# VGA.net
KiCad netlist of a schematic drawn in Altium Designer
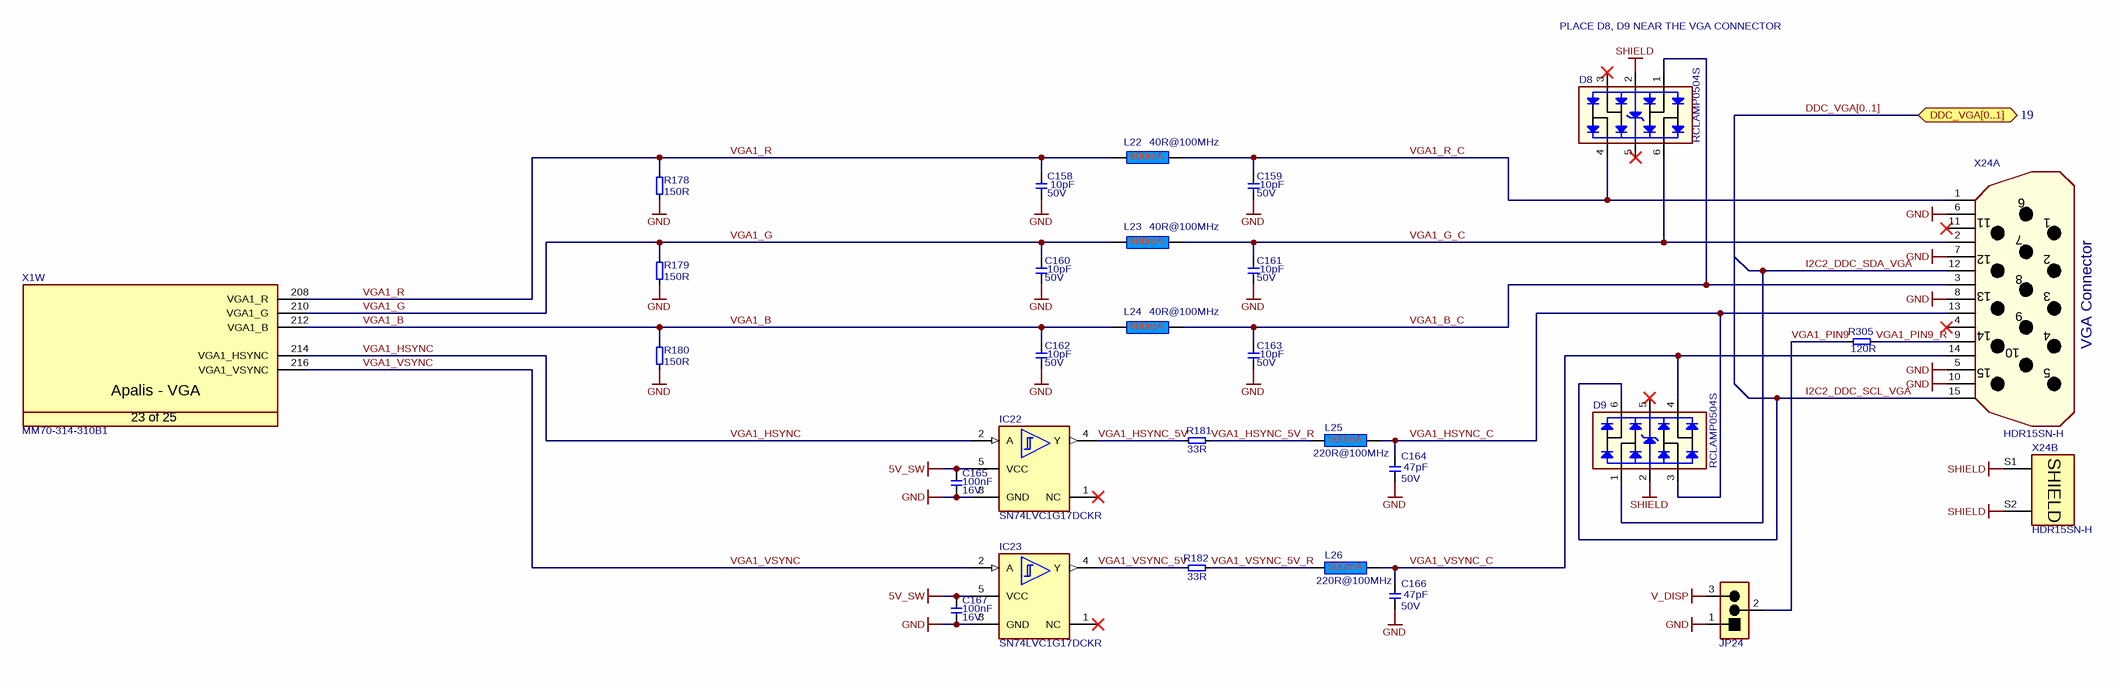
[diagram p0: VGA.SchDoc]

(export (version "E")
  (design (tool "Eeschema 10.0.6"))
  (components
    (comp (ref "C158")
      (value "10pF")
      (footprint "T_CAPC0603X33N")
      (description "Capacitor Ceramic NP0 10pF 50V 10% 0603")
      (fields (field (name "TOLERANCE") "10%") (field (name "RATING") "50V"))
      (libsource (lib "Apalis Evaluation Board") (part "C-NP0-10pF-50V-10%-0603"))
    )
    (comp (ref "C159")
      (value "10pF")
      (footprint "T_CAPC0603X33N")
      (description "Capacitor Ceramic NP0 10pF 50V 10% 0603")
      (fields (field (name "TOLERANCE") "10%") (field (name "RATING") "50V"))
      (libsource (lib "Apalis Evaluation Board") (part "C-NP0-10pF-50V-10%-0603"))
    )
    (comp (ref "C160")
      (value "10pF")
      (footprint "T_CAPC0603X33N")
      (description "Capacitor Ceramic NP0 10pF 50V 10% 0603")
      (fields (field (name "TOLERANCE") "10%") (field (name "RATING") "50V"))
      (libsource (lib "Apalis Evaluation Board") (part "C-NP0-10pF-50V-10%-0603"))
    )
    (comp (ref "C161")
      (value "10pF")
      (footprint "T_CAPC0603X33N")
      (description "Capacitor Ceramic NP0 10pF 50V 10% 0603")
      (fields (field (name "TOLERANCE") "10%") (field (name "RATING") "50V"))
      (libsource (lib "Apalis Evaluation Board") (part "C-NP0-10pF-50V-10%-0603"))
    )
    (comp (ref "C162")
      (value "10pF")
      (footprint "T_CAPC0603X33N")
      (description "Capacitor Ceramic NP0 10pF 50V 10% 0603")
      (fields (field (name "TOLERANCE") "10%") (field (name "RATING") "50V"))
      (libsource (lib "Apalis Evaluation Board") (part "C-NP0-10pF-50V-10%-0603"))
    )
    (comp (ref "C163")
      (value "10pF")
      (footprint "T_CAPC0603X33N")
      (description "Capacitor Ceramic NP0 10pF 50V 10% 0603")
      (fields (field (name "TOLERANCE") "10%") (field (name "RATING") "50V"))
      (libsource (lib "Apalis Evaluation Board") (part "C-NP0-10pF-50V-10%-0603"))
    )
    (comp (ref "C164")
      (value "47pF")
      (footprint "T_CAPC0603X33N")
      (description "Capacitor Ceramic NP0 47pF 50V 10% 0603")
      (fields (field (name "TOLERANCE") "10%") (field (name "RATING") "50V"))
      (libsource (lib "Apalis Evaluation Board") (part "C-NP0-47pF-50V-10%-0603"))
    )
    (comp (ref "C165")
      (value "100nF")
      (footprint "T_CAPC0603X33N")
      (description "Capacitor Ceramic X7R 100nF 16V 10% 0603")
      (fields (field (name "TOLERANCE") "10%") (field (name "RATING") "16V"))
      (libsource (lib "Apalis Evaluation Board") (part "C-X7R-100nF-16V-10%-0603"))
    )
    (comp (ref "C166")
      (value "47pF")
      (footprint "T_CAPC0603X33N")
      (description "Capacitor Ceramic NP0 47pF 50V 10% 0603")
      (fields (field (name "TOLERANCE") "10%") (field (name "RATING") "50V"))
      (libsource (lib "Apalis Evaluation Board") (part "C-NP0-47pF-50V-10%-0603"))
    )
    (comp (ref "C167")
      (value "100nF")
      (footprint "T_CAPC0603X33N")
      (description "Capacitor Ceramic X7R 100nF 16V 10% 0603")
      (fields (field (name "TOLERANCE") "10%") (field (name "RATING") "16V"))
      (libsource (lib "Apalis Evaluation Board") (part "C-X7R-100nF-16V-10%-0603"))
    )
    (comp (ref "D8")
      (value "RCLAMP0504S")
      (footprint "T_SOT95P285X90-6N")
      (description "TVS Array low cap")
      (fields (field (name "MANUFACTURER PART NO.") "RCLAMP0504S"))
      (libsource (lib "Apalis Evaluation Board") (part "D-Semtech-RClamp0504S"))
    )
    (comp (ref "D9")
      (value "RCLAMP0504S")
      (footprint "T_SOT95P285X90-6N")
      (description "TVS Array low cap")
      (fields (field (name "MANUFACTURER PART NO.") "RCLAMP0504S"))
      (libsource (lib "") (part "D-Semtech-RClamp0504S_1"))
    )
    (comp (ref "IC22")
      (value "SN74LVC1G17DCKR")
      (footprint "SOT65P210X110-5N")
      (description "Single Schmitt-Trigger Buffer")
      (fields (field (name "MANUFACTURER PART NO.") "SN74LVC1G17DCKR"))
      (libsource (lib "Apalis Evaluation Board") (part "IC-TI-SN74LVC1G17DCKR"))
    )
    (comp (ref "IC23")
      (value "SN74LVC1G17DCKR")
      (footprint "SOT65P210X110-5N")
      (description "Single Schmitt-Trigger Buffer")
      (fields (field (name "MANUFACTURER PART NO.") "SN74LVC1G17DCKR"))
      (libsource (lib "Apalis Evaluation Board") (part "IC-TI-SN74LVC1G17DCKR"))
    )
    (comp (ref "JP24")
      (value "826936-3")
      (footprint "T_TYCO_826936-3")
      (description "Jumper, 3-Pin")
      (libsource (lib "Apalis Evaluation Board") (part "CON-Tyco-826936-3-1X3-2.54mm-JP_1"))
    )
    (comp (ref "L22")
      (value "40R@100MHz")
      (footprint "INDC1608X95N")
      (description "40R@100MHz 600mA EMI FILTER")
      (fields (field (name "TOLERANCE") "25%") (field (name "MANUFACTURER PART NO.") "MMZ1608S400A"))
      (libsource (lib "Apalis Evaluation Board") (part "L-TDK-MMZ1608S400A-40R@100MHz-600mA-25%-0603"))
    )
    (comp (ref "L23")
      (value "40R@100MHz")
      (footprint "INDC1608X95N")
      (description "40R@100MHz 600mA EMI FILTER")
      (fields (field (name "TOLERANCE") "25%") (field (name "MANUFACTURER PART NO.") "MMZ1608S400A"))
      (libsource (lib "Apalis Evaluation Board") (part "L-TDK-MMZ1608S400A-40R@100MHz-600mA-25%-0603"))
    )
    (comp (ref "L24")
      (value "40R@100MHz")
      (footprint "INDC1608X95N")
      (description "40R@100MHz 600mA EMI FILTER")
      (fields (field (name "TOLERANCE") "25%") (field (name "MANUFACTURER PART NO.") "MMZ1608S400A"))
      (libsource (lib "Apalis Evaluation Board") (part "L-TDK-MMZ1608S400A-40R@100MHz-600mA-25%-0603"))
    )
    (comp (ref "L25")
      (value "220R@100MHz")
      (footprint "INDC1608X95N")
      (description "220R@100MHz 500mA EMI FILTER")
      (fields (field (name "TOLERANCE") "25%"))
      (libsource (lib "Apalis Evaluation Board") (part "L-220R@100MHz-500mA-25%-0603"))
    )
    (comp (ref "L26")
      (value "220R@100MHz")
      (footprint "INDC1608X95N")
      (description "220R@100MHz 500mA EMI FILTER")
      (fields (field (name "TOLERANCE") "25%"))
      (libsource (lib "Apalis Evaluation Board") (part "L-220R@100MHz-500mA-25%-0603"))
    )
    (comp (ref "R178")
      (value "150R")
      (footprint "T_RESC0603X30N")
      (description "Resistor 150 ohm 63mW 1% 0603")
      (fields (field (name "TOLERANCE") "1%"))
      (libsource (lib "Apalis Evaluation Board") (part "R-150R-63mW-1%-0603"))
    )
    (comp (ref "R179")
      (value "150R")
      (footprint "T_RESC0603X30N")
      (description "Resistor 150 ohm 63mW 1% 0603")
      (fields (field (name "TOLERANCE") "1%"))
      (libsource (lib "Apalis Evaluation Board") (part "R-150R-63mW-1%-0603"))
    )
    (comp (ref "R180")
      (value "150R")
      (footprint "T_RESC0603X30N")
      (description "Resistor 150 ohm 63mW 1% 0603")
      (fields (field (name "TOLERANCE") "1%"))
      (libsource (lib "Apalis Evaluation Board") (part "R-150R-63mW-1%-0603"))
    )
    (comp (ref "R181")
      (value "33R")
      (footprint "t_RESC0603X30N")
      (description "Resistor 33 ohm 63mW 5% 0603")
      (fields (field (name "TOLERANCE") "5%"))
      (libsource (lib "Apalis Evaluation Board") (part "R-33R-63mW-5%-0603"))
    )
    (comp (ref "R182")
      (value "33R")
      (footprint "t_RESC0603X30N")
      (description "Resistor 33 ohm 63mW 5% 0603")
      (fields (field (name "TOLERANCE") "5%"))
      (libsource (lib "Apalis Evaluation Board") (part "R-33R-63mW-5%-0603"))
    )
    (comp (ref "R305")
      (value "120R")
      (footprint "T_RESC0603X30N")
      (description "Resistor 120 ohm 250mW 5% 0603")
      (fields (field (name "TOLERANCE") "5%"))
      (libsource (lib "Apalis Evaluation Board") (part "R-120R-250mW-5%-0603"))
    )
    (comp (ref "X1")
      (value "CON-JAE-MM70-314-310B1-314-0.5mm")
      (footprint "T_JAE_MM70-314-310B1")
      (description "MXM3 Connector")
      (fields (field (name "MANUFACTURER PART NO.") "MM70-314-310B1"))
      (libsource (lib "Apalis Evaluation Board") (part "CON-JAE-MM70-314-310B1-314-0.5mm"))
    )
    (comp (ref "X24")
      (value "HDR15SN-H")
      (footprint "T_AUK_HDR15SN-H")
      (description "15 pin male D-SUB connector")
      (fields (field (name "MANUFACTURER PART NO.") "HDR15SN-H"))
      (libsource (lib "Apalis Evaluation Board") (part "CON-AUK-HDR15SN-H"))
    )
  )
  (nets
    (net (code "4") (name "/I2C2_DDC_SCL_VGA") (class "Default")
      (node (ref "D9") (pin "6") (pinfunction "6_6") (pintype "power_in"))
      (node (ref "X24") (pin "15") (pinfunction "RI_15") (pintype "passive"))
    )
    (net (code "5") (name "/I2C2_DDC_SDA_VGA") (class "Default")
      (node (ref "D9") (pin "1") (pinfunction "1_1") (pintype "power_in"))
      (node (ref "X24") (pin "12") (pinfunction "RI_12") (pintype "passive"))
    )
    (net (code "6") (name "/VGA1_B") (class "Default")
      (node (ref "C162") (pin "1") (pinfunction "1_1") (pintype "passive"))
      (node (ref "L24") (pin "1") (pinfunction "1_1") (pintype "passive"))
      (node (ref "R180") (pin "2") (pinfunction "2_2") (pintype "passive"))
      (node (ref "X1") (pin "212") (pinfunction "VGA1_B_212") (pintype "passive"))
    )
    (net (code "7") (name "/VGA1_B_C") (class "Default")
      (node (ref "C163") (pin "1") (pinfunction "1_1") (pintype "passive"))
      (node (ref "D8") (pin "1") (pinfunction "1_1") (pintype "power_in"))
      (node (ref "L24") (pin "2") (pinfunction "2_2") (pintype "passive"))
      (node (ref "X24") (pin "3") (pinfunction "TXD_3") (pintype "passive"))
    )
    (net (code "8") (name "/VGA1_G") (class "Default")
      (node (ref "C160") (pin "1") (pinfunction "1_1") (pintype "passive"))
      (node (ref "L23") (pin "1") (pinfunction "1_1") (pintype "passive"))
      (node (ref "R179") (pin "2") (pinfunction "2_2") (pintype "passive"))
      (node (ref "X1") (pin "210") (pinfunction "VGA1_G_210") (pintype "passive"))
    )
    (net (code "9") (name "/VGA1_G_C") (class "Default")
      (node (ref "C161") (pin "1") (pinfunction "1_1") (pintype "passive"))
      (node (ref "D8") (pin "6") (pinfunction "6_6") (pintype "power_in"))
      (node (ref "L23") (pin "2") (pinfunction "2_2") (pintype "passive"))
      (node (ref "X24") (pin "2") (pinfunction "RXD_2") (pintype "passive"))
    )
    (net (code "10") (name "/VGA1_HSYNC") (class "Default")
      (node (ref "IC22") (pin "2") (pinfunction "A_2") (pintype "input"))
      (node (ref "X1") (pin "214") (pinfunction "VGA1_HSYNC_214") (pintype "passive"))
    )
    (net (code "11") (name "/VGA1_HSYNC_5V") (class "Default")
      (node (ref "IC22") (pin "4") (pinfunction "Y_4") (pintype "output"))
      (node (ref "R181") (pin "1") (pinfunction "1_1") (pintype "passive"))
    )
    (net (code "12") (name "/VGA1_HSYNC_5V_R") (class "Default")
      (node (ref "L25") (pin "1") (pinfunction "1_1") (pintype "passive"))
      (node (ref "R181") (pin "2") (pinfunction "2_2") (pintype "passive"))
    )
    (net (code "13") (name "/VGA1_HSYNC_C") (class "Default")
      (node (ref "C164") (pin "1") (pinfunction "1_1") (pintype "passive"))
      (node (ref "D9") (pin "3") (pinfunction "3_3") (pintype "power_in"))
      (node (ref "L25") (pin "2") (pinfunction "2_2") (pintype "passive"))
      (node (ref "X24") (pin "13") (pinfunction "RI_13") (pintype "passive"))
    )
    (net (code "14") (name "/VGA1_PIN9") (class "Default")
      (node (ref "JP24") (pin "2") (pinfunction "2_2") (pintype "passive"))
      (node (ref "R305") (pin "1") (pinfunction "1_1") (pintype "passive"))
    )
    (net (code "15") (name "/VGA1_PIN9_R") (class "Default")
      (node (ref "R305") (pin "2") (pinfunction "2_2") (pintype "passive"))
      (node (ref "X24") (pin "9") (pinfunction "RI_9") (pintype "passive"))
    )
    (net (code "16") (name "/VGA1_R") (class "Default")
      (node (ref "C158") (pin "1") (pinfunction "1_1") (pintype "passive"))
      (node (ref "L22") (pin "1") (pinfunction "1_1") (pintype "passive"))
      (node (ref "R178") (pin "2") (pinfunction "2_2") (pintype "passive"))
      (node (ref "X1") (pin "208") (pinfunction "VGA1_R_208") (pintype "passive"))
    )
    (net (code "17") (name "/VGA1_R_C") (class "Default")
      (node (ref "C159") (pin "1") (pinfunction "1_1") (pintype "passive"))
      (node (ref "D8") (pin "4") (pinfunction "4_4") (pintype "power_in"))
      (node (ref "L22") (pin "2") (pinfunction "2_2") (pintype "passive"))
      (node (ref "X24") (pin "1") (pinfunction "DCD_1") (pintype "passive"))
    )
    (net (code "18") (name "/VGA1_VSYNC") (class "Default")
      (node (ref "IC23") (pin "2") (pinfunction "A_2") (pintype "input"))
      (node (ref "X1") (pin "216") (pinfunction "VGA1_VSYNC_216") (pintype "passive"))
    )
    (net (code "19") (name "/VGA1_VSYNC_5V") (class "Default")
      (node (ref "IC23") (pin "4") (pinfunction "Y_4") (pintype "output"))
      (node (ref "R182") (pin "1") (pinfunction "1_1") (pintype "passive"))
    )
    (net (code "20") (name "/VGA1_VSYNC_5V_R") (class "Default")
      (node (ref "L26") (pin "1") (pinfunction "1_1") (pintype "passive"))
      (node (ref "R182") (pin "2") (pinfunction "2_2") (pintype "passive"))
    )
    (net (code "21") (name "/VGA1_VSYNC_C") (class "Default")
      (node (ref "C166") (pin "1") (pinfunction "1_1") (pintype "passive"))
      (node (ref "D9") (pin "4") (pinfunction "4_4") (pintype "power_in"))
      (node (ref "L26") (pin "2") (pinfunction "2_2") (pintype "passive"))
      (node (ref "X24") (pin "14") (pinfunction "RI_14") (pintype "passive"))
    )
    (net (code "22") (name "5V_SW") (class "Default")
      (node (ref "C165") (pin "2") (pinfunction "2_2") (pintype "passive"))
      (node (ref "C167") (pin "2") (pinfunction "2_2") (pintype "passive"))
      (node (ref "IC22") (pin "5") (pinfunction "VCC_5") (pintype "power_in"))
      (node (ref "IC23") (pin "5") (pinfunction "VCC_5") (pintype "power_in"))
    )
    (net (code "23") (name "GND") (class "Default")
      (node (ref "C158") (pin "2") (pinfunction "2_2") (pintype "passive"))
      (node (ref "C159") (pin "2") (pinfunction "2_2") (pintype "passive"))
      (node (ref "C160") (pin "2") (pinfunction "2_2") (pintype "passive"))
      (node (ref "C161") (pin "2") (pinfunction "2_2") (pintype "passive"))
      (node (ref "C162") (pin "2") (pinfunction "2_2") (pintype "passive"))
      (node (ref "C163") (pin "2") (pinfunction "2_2") (pintype "passive"))
      (node (ref "C164") (pin "2") (pinfunction "2_2") (pintype "passive"))
      (node (ref "C165") (pin "1") (pinfunction "1_1") (pintype "passive"))
      (node (ref "C166") (pin "2") (pinfunction "2_2") (pintype "passive"))
      (node (ref "C167") (pin "1") (pinfunction "1_1") (pintype "passive"))
      (node (ref "IC22") (pin "3") (pinfunction "GND_3") (pintype "power_in"))
      (node (ref "IC23") (pin "3") (pinfunction "GND_3") (pintype "power_in"))
      (node (ref "JP24") (pin "1") (pinfunction "1_1") (pintype "passive"))
      (node (ref "R178") (pin "1") (pinfunction "1_1") (pintype "passive"))
      (node (ref "R179") (pin "1") (pinfunction "1_1") (pintype "passive"))
      (node (ref "R180") (pin "1") (pinfunction "1_1") (pintype "passive"))
      (node (ref "X24") (pin "10") (pinfunction "RI_10") (pintype "passive"))
      (node (ref "X24") (pin "5") (pinfunction "GND_5") (pintype "passive"))
      (node (ref "X24") (pin "6") (pinfunction "DSR_6") (pintype "passive"))
      (node (ref "X24") (pin "7") (pinfunction "RTS_7") (pintype "passive"))
      (node (ref "X24") (pin "8") (pinfunction "CTS_8") (pintype "passive"))
    )
    (net (code "24") (name "SHIELD") (class "Default")
      (node (ref "D8") (pin "2") (pinfunction "2_2") (pintype "power_in"))
      (node (ref "D9") (pin "2") (pinfunction "2_2") (pintype "power_in"))
      (node (ref "X24") (pin "S1") (pinfunction "SHIELD_S1") (pintype "passive"))
      (node (ref "X24") (pin "S2") (pinfunction "SHIELD_S2") (pintype "passive"))
    )
    (net (code "25") (name "V_DISP") (class "Default")
      (node (ref "JP24") (pin "3") (pinfunction "3_3") (pintype "passive"))
    )
    (net (code "26") (name "unconnected-(D8-Pad3)") (class "Default")
      (node (ref "D8") (pin "3") (pinfunction "3_3") (pintype "power_in+no_connect"))
    )
    (net (code "27") (name "unconnected-(D8-Pad5)") (class "Default")
      (node (ref "D8") (pin "5") (pinfunction "5_5") (pintype "power_in+no_connect"))
    )
    (net (code "28") (name "unconnected-(D9-Pad5)") (class "Default")
      (node (ref "D9") (pin "5") (pinfunction "5_5") (pintype "power_in+no_connect"))
    )
    (net (code "29") (name "unconnected-(IC22-NC-Pad1)") (class "Default")
      (node (ref "IC22") (pin "1") (pinfunction "NC_1") (pintype "passive+no_connect"))
    )
    (net (code "30") (name "unconnected-(IC23-NC-Pad1)") (class "Default")
      (node (ref "IC23") (pin "1") (pinfunction "NC_1") (pintype "passive+no_connect"))
    )
    (net (code "31") (name "unconnected-(X24A-DTR-Pad4)") (class "Default")
      (node (ref "X24") (pin "4") (pinfunction "DTR_4") (pintype "passive+no_connect"))
    )
    (net (code "32") (name "unconnected-(X24A-RI-Pad11)") (class "Default")
      (node (ref "X24") (pin "11") (pinfunction "RI_11") (pintype "passive+no_connect"))
    )
  )
)
